# USB_C_conn_ctrl.net
KiCad netlist of a schematic drawn in Altium Designer
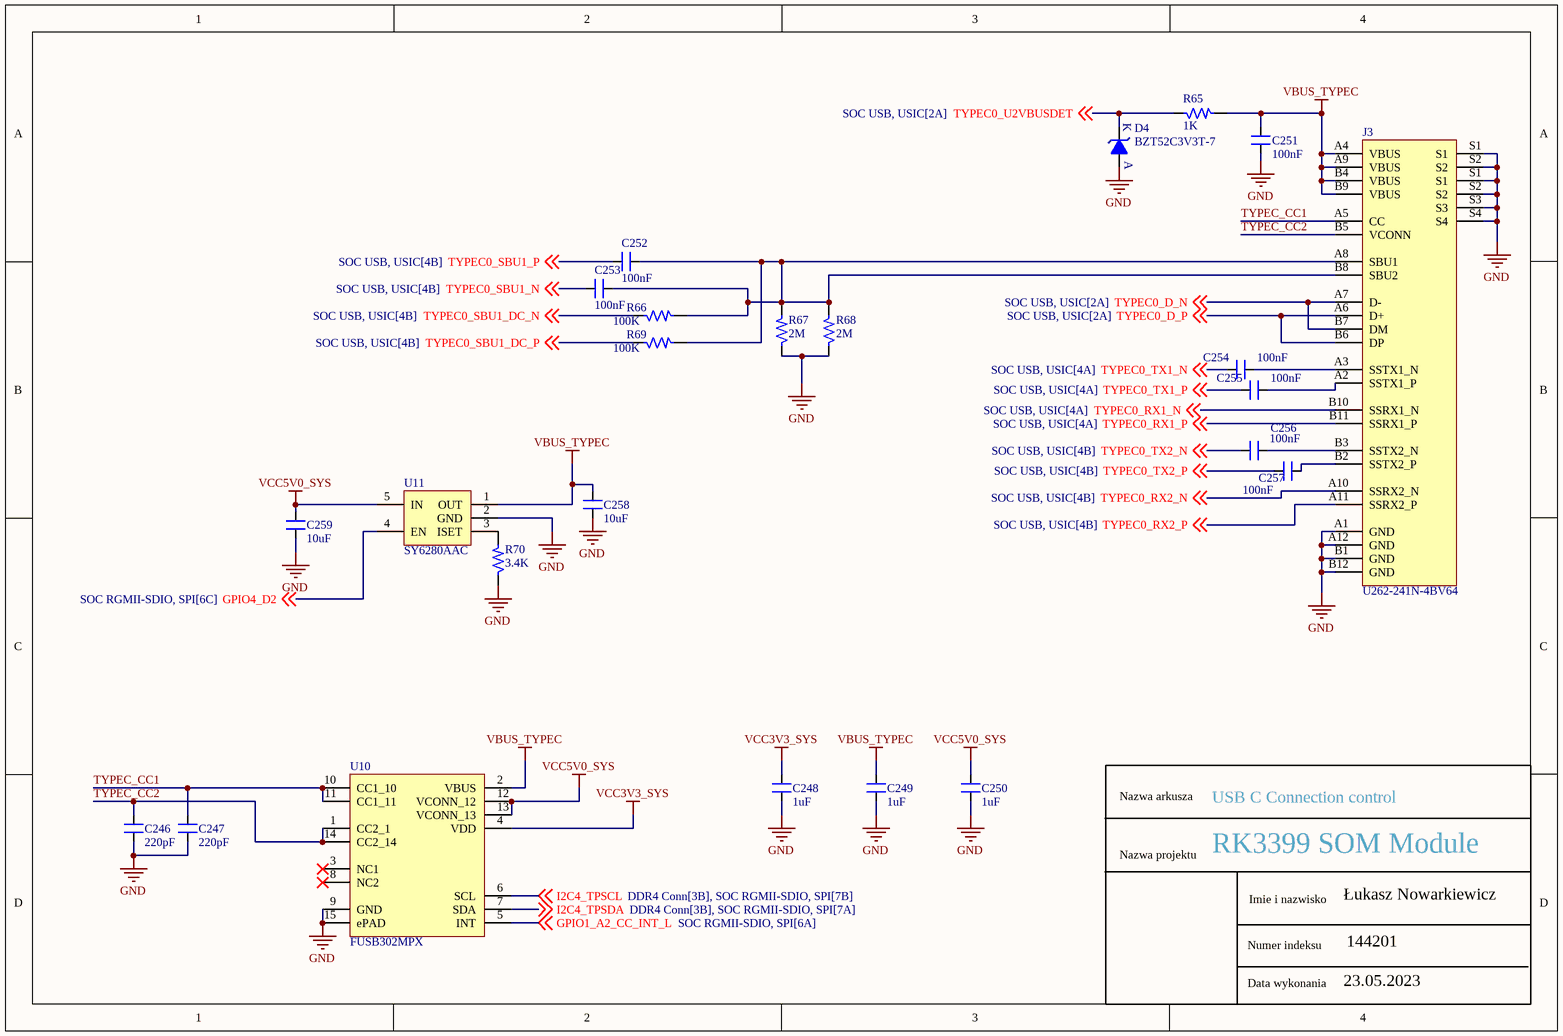
[diagram p0: USB C conn & ctrl.SchDoc]

(export (version "E")
  (design (tool "Eeschema 10.0.6"))
  (components
    (comp (ref "C246")
      (value "220pF")
      (footprint "CAP_0402")
      (description "220pF ±10% 10V Ceramic Capacitor X7R 0402 (1005 Metric)")
      (fields
        (field (name "MANUFACTURER") "KEMET")
        (field (name "MANUFACTURER PART NUMBER") "C0402C221K8RAC7867")
      )
      (libsource (lib "RK3399 _Module_Schlib") (part "CAP_220pF-10V-10%-0402"))
    )
    (comp (ref "C247")
      (value "220pF")
      (footprint "CAP_0402")
      (description "220pF ±10% 10V Ceramic Capacitor X7R 0402 (1005 Metric)")
      (fields
        (field (name "MANUFACTURER") "KEMET")
        (field (name "MANUFACTURER PART NUMBER") "C0402C221K8RAC7867")
      )
      (libsource (lib "RK3399 _Module_Schlib") (part "CAP_220pF-10V-10%-0402"))
    )
    (comp (ref "C248")
      (value "1uF")
      (footprint "CAP_0402")
      (description "1µF ±10% 10V Ceramic Capacitor X6S 0402 (1005 Metric)")
      (fields
        (field (name "MANUFACTURER") "Murata Electronics")
        (field (name "MANUFACTURER PART NUMBER") "GRT155C81A105KE01D")
      )
      (libsource (lib "RK3399 _Module_Schlib") (part "CAP_1uF-10V-10%-0402"))
    )
    (comp (ref "C249")
      (value "1uF")
      (footprint "CAP_0402")
      (description "1µF ±10% 10V Ceramic Capacitor X6S 0402 (1005 Metric)")
      (fields
        (field (name "MANUFACTURER") "Murata Electronics")
        (field (name "MANUFACTURER PART NUMBER") "GRT155C81A105KE01D")
      )
      (libsource (lib "RK3399 _Module_Schlib") (part "CAP_1uF-10V-10%-0402"))
    )
    (comp (ref "C250")
      (value "1uF")
      (footprint "CAP_0402")
      (description "1µF ±10% 10V Ceramic Capacitor X6S 0402 (1005 Metric)")
      (fields
        (field (name "MANUFACTURER") "Murata Electronics")
        (field (name "MANUFACTURER PART NUMBER") "GRT155C81A105KE01D")
      )
      (libsource (lib "RK3399 _Module_Schlib") (part "CAP_1uF-10V-10%-0402"))
    )
    (comp (ref "C251")
      (value "100nF")
      (footprint "CAP_0603")
      (description "0.1µF ±10% 10V Ceramic Capacitor X7R 0603 (1608 Metric)")
      (fields
        (field (name "MANUFACTURER") "Yageo")
        (field (name "MANUFACTURER PART NUMBER") "CC0603KRX7R6BB104")
      )
      (libsource (lib "RK3399 _Module_Schlib") (part "CAP_100nF-10V-5%-0603"))
    )
    (comp (ref "C252")
      (value "100nF")
      (footprint "CAP_0402")
      (description "0.1µF ±10% 25V Ceramic Capacitor X7R 0402 (1005 Metric)")
      (fields
        (field (name "MANUFACTURER") "Walsin Technology Corporation")
        (field (name "MANUFACTURER PART NUMBER") "0402B104K250CT")
      )
      (libsource (lib "RK3399 _Module_Schlib") (part "CAP_100nF-25V-10%-0402"))
    )
    (comp (ref "C253")
      (value "100nF")
      (footprint "CAP_0402")
      (description "0.1µF ±10% 25V Ceramic Capacitor X7R 0402 (1005 Metric)")
      (fields
        (field (name "MANUFACTURER") "Walsin Technology Corporation")
        (field (name "MANUFACTURER PART NUMBER") "0402B104K250CT")
      )
      (libsource (lib "RK3399 _Module_Schlib") (part "CAP_100nF-25V-10%-0402"))
    )
    (comp (ref "C254")
      (value "100nF")
      (footprint "CAP_0402")
      (description "0.1µF ±10% 25V Ceramic Capacitor X7R 0402 (1005 Metric)")
      (fields
        (field (name "MANUFACTURER") "Walsin Technology Corporation")
        (field (name "MANUFACTURER PART NUMBER") "0402B104K250CT")
      )
      (libsource (lib "RK3399 _Module_Schlib") (part "CAP_100nF-25V-10%-0402"))
    )
    (comp (ref "C255")
      (value "100nF")
      (footprint "CAP_0402")
      (description "0.1µF ±10% 25V Ceramic Capacitor X7R 0402 (1005 Metric)")
      (fields
        (field (name "MANUFACTURER") "Walsin Technology Corporation")
        (field (name "MANUFACTURER PART NUMBER") "0402B104K250CT")
      )
      (libsource (lib "RK3399 _Module_Schlib") (part "CAP_100nF-25V-10%-0402"))
    )
    (comp (ref "C256")
      (value "100nF")
      (footprint "CAP_0402")
      (description "0.1µF ±10% 25V Ceramic Capacitor X7R 0402 (1005 Metric)")
      (fields
        (field (name "MANUFACTURER") "Walsin Technology Corporation")
        (field (name "MANUFACTURER PART NUMBER") "0402B104K250CT")
      )
      (libsource (lib "RK3399 _Module_Schlib") (part "CAP_100nF-25V-10%-0402"))
    )
    (comp (ref "C257")
      (value "100nF")
      (footprint "CAP_0402")
      (description "0.1µF ±10% 25V Ceramic Capacitor X7R 0402 (1005 Metric)")
      (fields
        (field (name "MANUFACTURER") "Walsin Technology Corporation")
        (field (name "MANUFACTURER PART NUMBER") "0402B104K250CT")
      )
      (libsource (lib "RK3399 _Module_Schlib") (part "CAP_100nF-25V-10%-0402"))
    )
    (comp (ref "C258")
      (value "10uF")
      (footprint "CAP_0402")
      (description "10µF ±20% 10V Ceramic Capacitor X5R 0402 (1005 Metric)")
      (fields
        (field (name "MANUFACTURER PART NUMBER") "CL05A106MP5NUNC")
        (field (name "MANUFACTURER") "Samsung Electro-Mechanics")
      )
      (libsource (lib "RK3399 _Module_Schlib") (part "CAP_10uF-10V-20%-0402"))
    )
    (comp (ref "C259")
      (value "10uF")
      (footprint "CAP_0402")
      (description "10µF ±20% 10V Ceramic Capacitor X5R 0402 (1005 Metric)")
      (fields
        (field (name "MANUFACTURER PART NUMBER") "CL05A106MP5NUNC")
        (field (name "MANUFACTURER") "Samsung Electro-Mechanics")
      )
      (libsource (lib "RK3399 _Module_Schlib") (part "CAP_10uF-10V-20%-0402"))
    )
    (comp (ref "D4")
      (value "BZT52C3V3T-7")
      (footprint "DIO_SOD523")
      (description "Zener Diode 3.3V 300mW ±6% Surface Mount SOD-523")
      (fields (field (name "MANUFACTURER") "Diodes Incorporated"))
      (libsource (lib "RK3399 _Module_Schlib") (part "DIO-Z_3.3V-300mW-SOD-523"))
    )
    (comp (ref "J3")
      (value "U262-241N-4BV64")
      (footprint "CON24_19.64_U262-241N-4BV64_TH_RA")
      (description "USB - Type C Female 24 SMD USB Connectors RoHS")
      (fields (field (name "MANUFACTURER") "XKB Connectivity"))
      (libsource (lib "RK3399 _Module_Schlib") (part "CON-TYPEC_U262-241N-4BV64-SMD"))
    )
    (comp (ref "R65")
      (value "1K")
      (footprint "RES_0402")
      (description "1 kOhms ±1% 0.1W, 1/10W Chip Resistor 0402 (1005 Metric) Anti-Sulfur Thin Film")
      (fields
        (field (name "MANUFACTURER") "Vishay Beyschlag/Draloric/BC Components")
        (field (name "MANUFACTURER PART NUMBER") "MCS04020C1001FE000")
      )
      (libsource (lib "RK3399 _Module_Schlib") (part "RES_1K-0.1W-1%-0402"))
    )
    (comp (ref "R66")
      (value "100K")
      (footprint "RES_0402")
      (description "100 kOhms ±1% 0.1W, 1/10W Chip Resistor 0402 (1005 Metric) Anti-Sulfur Thin Film")
      (fields
        (field (name "MANUFACTURER") "Vishay Beyschlag/Draloric/BC Components")
        (field (name "MANUFACTURER PART NUMBER") "MCS04020C1003FE000")
      )
      (libsource (lib "RK3399 _Module_Schlib") (part "RES_100K-0.1W-1%-0402"))
    )
    (comp (ref "R67")
      (value "2M")
      (footprint "RES_0402")
      (description "2 MOhms ±1% 0.1W, 1/10W Chip Resistor 0402 (1005 Metric) Anti-Sulfur Thin Film")
      (fields
        (field (name "MANUFACTURER") "Vishay Beyschlag/Draloric/BC Components")
        (field (name "MANUFACTURER PART NUMBER") "MCS04020C2004FE000")
      )
      (libsource (lib "RK3399 _Module_Schlib") (part "RES_2M-0.1W-1%-0402"))
    )
    (comp (ref "R68")
      (value "2M")
      (footprint "RES_0402")
      (description "2 MOhms ±1% 0.1W, 1/10W Chip Resistor 0402 (1005 Metric) Anti-Sulfur Thin Film")
      (fields
        (field (name "MANUFACTURER") "Vishay Beyschlag/Draloric/BC Components")
        (field (name "MANUFACTURER PART NUMBER") "MCS04020C2004FE000")
      )
      (libsource (lib "RK3399 _Module_Schlib") (part "RES_2M-0.1W-1%-0402"))
    )
    (comp (ref "R69")
      (value "100K")
      (footprint "RES_0402")
      (description "100 kOhms ±1% 0.1W, 1/10W Chip Resistor 0402 (1005 Metric) Anti-Sulfur Thin Film")
      (fields
        (field (name "MANUFACTURER") "Vishay Beyschlag/Draloric/BC Components")
        (field (name "MANUFACTURER PART NUMBER") "MCS04020C1003FE000")
      )
      (libsource (lib "RK3399 _Module_Schlib") (part "RES_100K-0.1W-1%-0402"))
    )
    (comp (ref "R70")
      (value "3.4K")
      (footprint "RES_0402")
      (description "3.4 kOhms ±1% 0.1W, 1/10W Chip Resistor 0402 (1005 Metric) Automotive AEC-Q200 Thick Film")
      (fields
        (field (name "MANUFACTURER") "Panasonic Electronic Components")
        (field (name "MANUFACTURER PART NUMBER") "ERJ-2RKF3401X")
      )
      (libsource (lib "RK3399 _Module_Schlib") (part "RES_3.4K-0.1W-1%-0402"))
    )
    (comp (ref "U10")
      (value "FUSB302MPX")
      (footprint "MLP-14_98.4X98.4_SMD")
      (description "USB Controller USB 3.1 USB Interface 14-MLP (2.5x2.5)")
      (fields (field (name "MANUFACTURER") "ON Semiconductor"))
      (libsource (lib "RK3399 _Module_Schlib") (part "IC_FUSB302MPX"))
    )
    (comp (ref "U11")
      (value "SY6280AAC")
      (footprint "SOT23-5")
      (description "SOT-23-5 PMIC - Power Distribution Switches RoHS")
      (fields (field (name "MANUFACTURER") "Silergy Corp"))
      (libsource (lib "RK3399 _Module_Schlib") (part "REG-ADJ_5.5V-5.5V-1.25A-SOT-23-5"))
    )
  )
  (nets
    (net (code "1") (name "/TYPEC_CC1") (class "Default")
      (node (ref "C247") (pin "2") (pinfunction "2_2") (pintype "passive"))
      (node (ref "J3") (pin "A5") (pinfunction "CC_A5") (pintype "passive"))
      (node (ref "U10") (pin "10") (pinfunction "CC1_10_10") (pintype "passive"))
      (node (ref "U10") (pin "11") (pinfunction "CC1_11_11") (pintype "passive"))
    )
    (net (code "2") (name "/TYPEC_CC2") (class "Default")
      (node (ref "C246") (pin "2") (pinfunction "2_2") (pintype "passive"))
      (node (ref "J3") (pin "B5") (pinfunction "VCONN_B5") (pintype "passive"))
      (node (ref "U10") (pin "1") (pinfunction "CC2_1_1") (pintype "passive"))
      (node (ref "U10") (pin "14") (pinfunction "CC2_14_14") (pintype "passive"))
    )
    (net (code "3") (name "GND") (class "Default")
      (node (ref "C246") (pin "1") (pinfunction "1_1") (pintype "passive"))
      (node (ref "C247") (pin "1") (pinfunction "1_1") (pintype "passive"))
      (node (ref "C248") (pin "1") (pinfunction "1_1") (pintype "passive"))
      (node (ref "C249") (pin "1") (pinfunction "1_1") (pintype "passive"))
      (node (ref "C250") (pin "1") (pinfunction "1_1") (pintype "passive"))
      (node (ref "C251") (pin "1") (pinfunction "1_1") (pintype "passive"))
      (node (ref "C258") (pin "1") (pinfunction "1_1") (pintype "passive"))
      (node (ref "C259") (pin "1") (pinfunction "1_1") (pintype "passive"))
      (node (ref "D4") (pin "A") (pinfunction "A_A") (pintype "passive"))
      (node (ref "J3") (pin "A1") (pinfunction "GND_A1") (pintype "passive"))
      (node (ref "J3") (pin "A12") (pinfunction "GND_A12") (pintype "passive"))
      (node (ref "J3") (pin "B1") (pinfunction "GND_B1") (pintype "passive"))
      (node (ref "J3") (pin "B12") (pinfunction "GND_B12") (pintype "passive"))
      (node (ref "J3") (pin "S1") (pinfunction "S1_S1") (pintype "passive"))
      (node (ref "J3") (pin "S2") (pinfunction "S2_S2") (pintype "passive"))
      (node (ref "J3") (pin "S3") (pinfunction "S3_S3") (pintype "passive"))
      (node (ref "J3") (pin "S4") (pinfunction "S4_S4") (pintype "passive"))
      (node (ref "R67") (pin "1") (pinfunction "1_1") (pintype "passive"))
      (node (ref "R68") (pin "1") (pinfunction "1_1") (pintype "passive"))
      (node (ref "R70") (pin "1") (pinfunction "1_1") (pintype "passive"))
      (node (ref "U10") (pin "15") (pinfunction "ePAD_15") (pintype "passive"))
      (node (ref "U10") (pin "9") (pinfunction "GND_9") (pintype "passive"))
      (node (ref "U11") (pin "2") (pinfunction "GND_2") (pintype "passive"))
    )
    (net (code "4") (name "GPIO1_A2_CC_INT_L") (class "Default")
      (node (ref "U10") (pin "5") (pinfunction "INT_5") (pintype "passive"))
    )
    (net (code "5") (name "GPIO4_D2") (class "Default")
      (node (ref "U11") (pin "4") (pinfunction "EN_4") (pintype "passive"))
    )
    (net (code "6") (name "I2C4_TPSCL") (class "Default")
      (node (ref "U10") (pin "6") (pinfunction "SCL_6") (pintype "passive"))
    )
    (net (code "7") (name "I2C4_TPSDA") (class "Default")
      (node (ref "U10") (pin "7") (pinfunction "SDA_7") (pintype "passive"))
    )
    (net (code "8") (name "Net-(J3-SBU1)") (class "Default")
      (node (ref "C252") (pin "2") (pinfunction "2_2") (pintype "passive"))
      (node (ref "C253") (pin "2") (pinfunction "2_2") (pintype "passive"))
      (node (ref "J3") (pin "A8") (pinfunction "SBU1_A8") (pintype "passive"))
      (node (ref "J3") (pin "B8") (pinfunction "SBU2_B8") (pintype "passive"))
      (node (ref "R66") (pin "2") (pinfunction "2_2") (pintype "passive"))
      (node (ref "R67") (pin "2") (pinfunction "2_2") (pintype "passive"))
      (node (ref "R68") (pin "2") (pinfunction "2_2") (pintype "passive"))
      (node (ref "R69") (pin "2") (pinfunction "2_2") (pintype "passive"))
    )
    (net (code "9") (name "Net-(J3-SSTX1_N)") (class "Default")
      (node (ref "C254") (pin "2") (pinfunction "2_2") (pintype "passive"))
      (node (ref "J3") (pin "A3") (pinfunction "SSTX1_N_A3") (pintype "passive"))
    )
    (net (code "10") (name "Net-(J3-SSTX1_P)") (class "Default")
      (node (ref "C255") (pin "2") (pinfunction "2_2") (pintype "passive"))
      (node (ref "J3") (pin "A2") (pinfunction "SSTX1_P_A2") (pintype "passive"))
    )
    (net (code "11") (name "Net-(J3-SSTX2_N)") (class "Default")
      (node (ref "C256") (pin "2") (pinfunction "2_2") (pintype "passive"))
      (node (ref "J3") (pin "B3") (pinfunction "SSTX2_N_B3") (pintype "passive"))
    )
    (net (code "12") (name "Net-(J3-SSTX2_P)") (class "Default")
      (node (ref "C257") (pin "2") (pinfunction "2_2") (pintype "passive"))
      (node (ref "J3") (pin "B2") (pinfunction "SSTX2_P_B2") (pintype "passive"))
    )
    (net (code "13") (name "Net-(U11-ISET)") (class "Default")
      (node (ref "R70") (pin "2") (pinfunction "2_2") (pintype "passive"))
      (node (ref "U11") (pin "3") (pinfunction "ISET_3") (pintype "passive"))
    )
    (net (code "14") (name "TYPEC0_D_N") (class "Default")
      (node (ref "J3") (pin "A7") (pinfunction "D-_A7") (pintype "passive"))
      (node (ref "J3") (pin "B7") (pinfunction "DM_B7") (pintype "passive"))
    )
    (net (code "15") (name "TYPEC0_D_P") (class "Default")
      (node (ref "J3") (pin "A6") (pinfunction "D+_A6") (pintype "passive"))
      (node (ref "J3") (pin "B6") (pinfunction "DP_B6") (pintype "passive"))
    )
    (net (code "16") (name "TYPEC0_RX1_N") (class "Default")
      (node (ref "J3") (pin "B10") (pinfunction "SSRX1_N_B10") (pintype "passive"))
    )
    (net (code "17") (name "TYPEC0_RX1_P") (class "Default")
      (node (ref "J3") (pin "B11") (pinfunction "SSRX1_P_B11") (pintype "passive"))
    )
    (net (code "18") (name "TYPEC0_RX2_N") (class "Default")
      (node (ref "J3") (pin "A10") (pinfunction "SSRX2_N_A10") (pintype "passive"))
    )
    (net (code "19") (name "TYPEC0_RX2_P") (class "Default")
      (node (ref "J3") (pin "A11") (pinfunction "SSRX2_P_A11") (pintype "passive"))
    )
    (net (code "20") (name "TYPEC0_SBU1_DC_N") (class "Default")
      (node (ref "R66") (pin "1") (pinfunction "1_1") (pintype "passive"))
    )
    (net (code "21") (name "TYPEC0_SBU1_DC_P") (class "Default")
      (node (ref "R69") (pin "1") (pinfunction "1_1") (pintype "passive"))
    )
    (net (code "22") (name "TYPEC0_SBU1_N") (class "Default")
      (node (ref "C253") (pin "1") (pinfunction "1_1") (pintype "passive"))
    )
    (net (code "23") (name "TYPEC0_SBU1_P") (class "Default")
      (node (ref "C252") (pin "1") (pinfunction "1_1") (pintype "passive"))
    )
    (net (code "24") (name "TYPEC0_TX1_N") (class "Default")
      (node (ref "C254") (pin "1") (pinfunction "1_1") (pintype "passive"))
    )
    (net (code "25") (name "TYPEC0_TX1_P") (class "Default")
      (node (ref "C255") (pin "1") (pinfunction "1_1") (pintype "passive"))
    )
    (net (code "26") (name "TYPEC0_TX2_N") (class "Default")
      (node (ref "C256") (pin "1") (pinfunction "1_1") (pintype "passive"))
    )
    (net (code "27") (name "TYPEC0_TX2_P") (class "Default")
      (node (ref "C257") (pin "1") (pinfunction "1_1") (pintype "passive"))
    )
    (net (code "28") (name "TYPEC0_U2VBUSDET") (class "Default")
      (node (ref "D4") (pin "K") (pinfunction "K_K") (pintype "passive"))
      (node (ref "R65") (pin "1") (pinfunction "1_1") (pintype "passive"))
    )
    (net (code "29") (name "VBUS_TYPEC") (class "Default")
      (node (ref "C249") (pin "2") (pinfunction "2_2") (pintype "passive"))
      (node (ref "C251") (pin "2") (pinfunction "2_2") (pintype "passive"))
      (node (ref "C258") (pin "2") (pinfunction "2_2") (pintype "passive"))
      (node (ref "J3") (pin "A4") (pinfunction "VBUS_A4") (pintype "passive"))
      (node (ref "J3") (pin "A9") (pinfunction "VBUS_A9") (pintype "passive"))
      (node (ref "J3") (pin "B4") (pinfunction "VBUS_B4") (pintype "passive"))
      (node (ref "J3") (pin "B9") (pinfunction "VBUS_B9") (pintype "passive"))
      (node (ref "R65") (pin "2") (pinfunction "2_2") (pintype "passive"))
      (node (ref "U10") (pin "2") (pinfunction "VBUS_2") (pintype "passive"))
      (node (ref "U11") (pin "1") (pinfunction "OUT_1") (pintype "passive"))
    )
    (net (code "30") (name "VCC3V3_SYS") (class "Default")
      (node (ref "C248") (pin "2") (pinfunction "2_2") (pintype "passive"))
      (node (ref "U10") (pin "4") (pinfunction "VDD_4") (pintype "passive"))
    )
    (net (code "31") (name "VCC5V0_SYS") (class "Default")
      (node (ref "C250") (pin "2") (pinfunction "2_2") (pintype "passive"))
      (node (ref "C259") (pin "2") (pinfunction "2_2") (pintype "passive"))
      (node (ref "U10") (pin "12") (pinfunction "VCONN_12_12") (pintype "passive"))
      (node (ref "U10") (pin "13") (pinfunction "VCONN_13_13") (pintype "passive"))
      (node (ref "U11") (pin "5") (pinfunction "IN_5") (pintype "passive"))
    )
    (net (code "32") (name "unconnected-(U10-NC1-Pad3)") (class "Default")
      (node (ref "U10") (pin "3") (pinfunction "NC1_3") (pintype "passive+no_connect"))
    )
    (net (code "33") (name "unconnected-(U10-NC2-Pad8)") (class "Default")
      (node (ref "U10") (pin "8") (pinfunction "NC2_8") (pintype "passive+no_connect"))
    )
  )
)
